# bellCPU.net
KiCad netlist of a schematic drawn in EAGLE
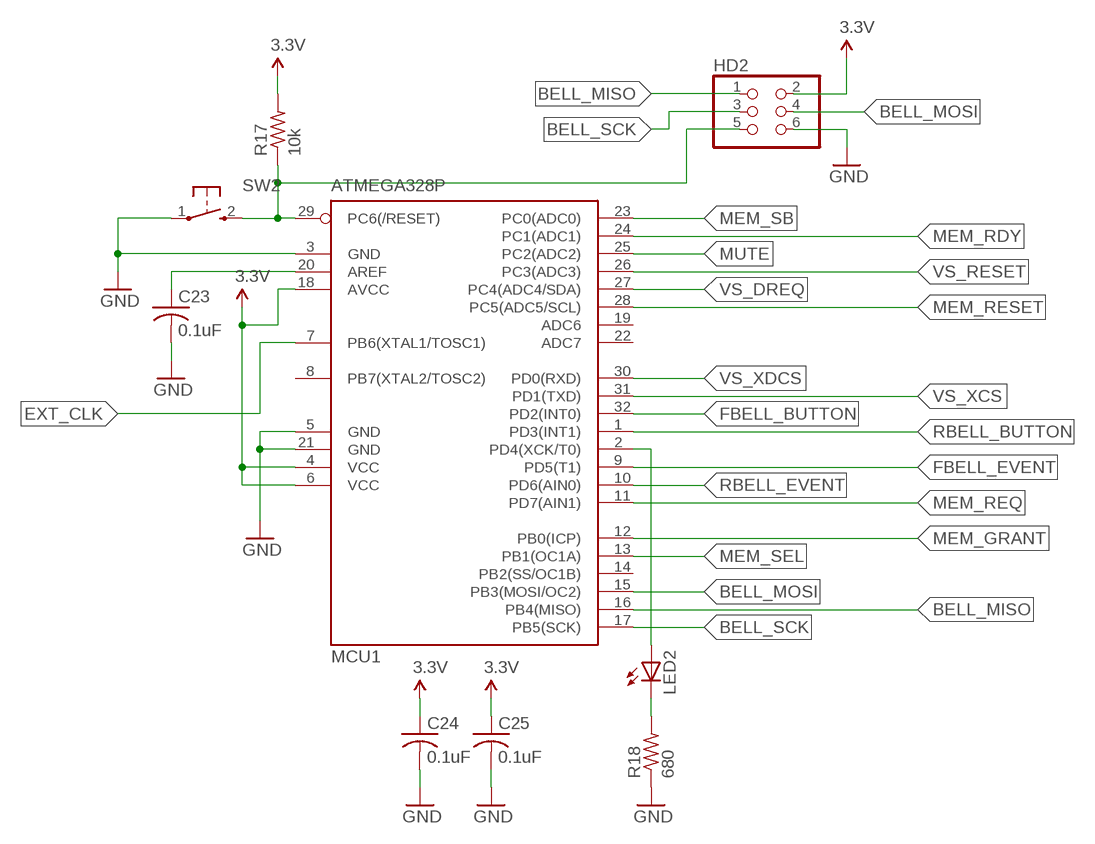
[diagram p0: schematic, sheet 1]

(export (version "E")
  (design (tool "Eeschema 10.0.6"))
  (components
    (comp (ref "C23")
      (value "0.1uF")
      (footprint "eagle-import:0603_CAP")
      (libsource (lib "eagle-import") (part "CAP0603"))
    )
    (comp (ref "C24")
      (value "0.1uF")
      (footprint "eagle-import:0603_CAP")
      (libsource (lib "eagle-import") (part "CAP0603"))
    )
    (comp (ref "C25")
      (value "0.1uF")
      (footprint "eagle-import:0603_CAP")
      (libsource (lib "eagle-import") (part "CAP0603"))
    )
    (comp (ref "HD2")
      (value "HEADER_2X3")
      (footprint "eagle-import:HEADER_2X3")
      (fields (field (name "MANF") "FCI"))
      (libsource (lib "eagle-import") (part "HEADER_2X3"))
    )
    (comp (ref "LED2")
      (value "LED0603")
      (footprint "eagle-import:0603_LED")
      (fields (field (name "MANF") "Avago Technologies"))
      (libsource (lib "eagle-import") (part "LED0603"))
    )
    (comp (ref "MCU1")
      (value "ATMEGA328P")
      (footprint "eagle-import:TQFP32-08")
      (fields (field (name "MANF") "Atmel"))
      (libsource (lib "eagle-import") (part "ATMEGA328P"))
    )
    (comp (ref "R17")
      (value "10k")
      (footprint "eagle-import:0603_RESISTOR")
      (libsource (lib "eagle-import") (part "RESISTOR0603"))
    )
    (comp (ref "R18")
      (value "680")
      (footprint "eagle-import:0603_RESISTOR")
      (libsource (lib "eagle-import") (part "RESISTOR0603"))
    )
    (comp (ref "SW2")
      (value "SWITCH")
      (footprint "eagle-import:SWITCH_TAC")
      (fields (field (name "MANF") "E-Switch"))
      (libsource (lib "eagle-import") (part "SWITCH"))
    )
  )
  (nets
    (net (code "1") (name "3.3V") (class "Default")
      (node (ref "C24") (pin "1") (pinfunction "1_1") (pintype "passive"))
      (node (ref "C25") (pin "1") (pinfunction "1_1") (pintype "passive"))
      (node (ref "HD2") (pin "2") (pinfunction "2_2") (pintype "passive"))
      (node (ref "MCU1") (pin "18") (pinfunction "AVCC_18") (pintype "power_in"))
      (node (ref "MCU1") (pin "4") (pinfunction "VCC_4") (pintype "power_in"))
      (node (ref "MCU1") (pin "6") (pinfunction "VCC_6") (pintype "power_in"))
      (node (ref "R17") (pin "2") (pinfunction "2_2") (pintype "passive"))
    )
    (net (code "2") (name "BELL_MISO") (class "Default")
      (node (ref "HD2") (pin "1") (pinfunction "1_1") (pintype "passive"))
      (node (ref "MCU1") (pin "16") (pinfunction "PB4(MISO)_16") (pintype "bidirectional"))
    )
    (net (code "3") (name "BELL_MOSI") (class "Default")
      (node (ref "HD2") (pin "4") (pinfunction "4_4") (pintype "passive"))
      (node (ref "MCU1") (pin "15") (pinfunction "PB3(MOSI/OC2)_15") (pintype "bidirectional"))
    )
    (net (code "4") (name "BELL_SCK") (class "Default")
      (node (ref "HD2") (pin "3") (pinfunction "3_3") (pintype "passive"))
      (node (ref "MCU1") (pin "17") (pinfunction "PB5(SCK)_17") (pintype "bidirectional"))
    )
    (net (code "5") (name "EXT_CLK") (class "Default")
      (node (ref "MCU1") (pin "7") (pinfunction "PB6(XTAL1/TOSC1)_7") (pintype "bidirectional"))
    )
    (net (code "6") (name "FBELL_BUTTON") (class "Default")
      (node (ref "MCU1") (pin "32") (pinfunction "PD2(INT0)_32") (pintype "bidirectional"))
    )
    (net (code "7") (name "FBELL_EVENT") (class "Default")
      (node (ref "MCU1") (pin "9") (pinfunction "PD5(T1)_9") (pintype "bidirectional"))
    )
    (net (code "8") (name "GND") (class "Default")
      (node (ref "C23") (pin "2") (pinfunction "2_2") (pintype "passive"))
      (node (ref "C24") (pin "2") (pinfunction "2_2") (pintype "passive"))
      (node (ref "C25") (pin "2") (pinfunction "2_2") (pintype "passive"))
      (node (ref "HD2") (pin "6") (pinfunction "6_6") (pintype "passive"))
      (node (ref "MCU1") (pin "21") (pinfunction "GND_21") (pintype "power_in"))
      (node (ref "MCU1") (pin "3") (pinfunction "GND_3") (pintype "power_in"))
      (node (ref "MCU1") (pin "5") (pinfunction "GND_5") (pintype "power_in"))
      (node (ref "R18") (pin "1") (pinfunction "1_1") (pintype "passive"))
      (node (ref "SW2") (pin "1") (pinfunction "1_1") (pintype "passive"))
    )
    (net (code "9") (name "MEM_GRANT") (class "Default")
      (node (ref "MCU1") (pin "12") (pinfunction "PB0(ICP)_12") (pintype "bidirectional"))
    )
    (net (code "10") (name "MEM_RDY") (class "Default")
      (node (ref "MCU1") (pin "24") (pinfunction "PC1(ADC1)_24") (pintype "bidirectional"))
    )
    (net (code "11") (name "MEM_REQ") (class "Default")
      (node (ref "MCU1") (pin "11") (pinfunction "PD7(AIN1)_11") (pintype "bidirectional"))
    )
    (net (code "12") (name "MEM_RESET") (class "Default")
      (node (ref "MCU1") (pin "28") (pinfunction "PC5(ADC5/SCL)_28") (pintype "bidirectional"))
    )
    (net (code "13") (name "MEM_SB") (class "Default")
      (node (ref "MCU1") (pin "23") (pinfunction "PC0(ADC0)_23") (pintype "bidirectional"))
    )
    (net (code "14") (name "MEM_SEL") (class "Default")
      (node (ref "MCU1") (pin "13") (pinfunction "PB1(OC1A)_13") (pintype "bidirectional"))
    )
    (net (code "15") (name "MUTE") (class "Default")
      (node (ref "MCU1") (pin "25") (pinfunction "PC2(ADC2)_25") (pintype "bidirectional"))
    )
    (net (code "16") (name "Net-(LED2-PadC)") (class "Default")
      (node (ref "LED2") (pin "C") (pinfunction "C_C") (pintype "passive"))
      (node (ref "R18") (pin "2") (pinfunction "2_2") (pintype "passive"))
    )
    (net (code "17") (name "Net-(MCU1-AREF)") (class "Default")
      (node (ref "C23") (pin "1") (pinfunction "1_1") (pintype "passive"))
      (node (ref "MCU1") (pin "20") (pinfunction "AREF_20") (pintype "passive"))
    )
    (net (code "18") (name "Net-(MCU1-PC6({slash}RESET))") (class "Default")
      (node (ref "HD2") (pin "5") (pinfunction "5_5") (pintype "passive"))
      (node (ref "MCU1") (pin "29") (pinfunction "PC6(/RESET)_29") (pintype "bidirectional"))
      (node (ref "R17") (pin "1") (pinfunction "1_1") (pintype "passive"))
      (node (ref "SW2") (pin "2") (pinfunction "2_2") (pintype "passive"))
    )
    (net (code "19") (name "Net-(MCU1-PD4(XCK{slash}T0))") (class "Default")
      (node (ref "LED2") (pin "A") (pinfunction "A_A") (pintype "passive"))
      (node (ref "MCU1") (pin "2") (pinfunction "PD4(XCK/T0)_2") (pintype "bidirectional"))
    )
    (net (code "20") (name "RBELL_BUTTON") (class "Default")
      (node (ref "MCU1") (pin "1") (pinfunction "PD3(INT1)_1") (pintype "bidirectional"))
    )
    (net (code "21") (name "RBELL_EVENT") (class "Default")
      (node (ref "MCU1") (pin "10") (pinfunction "PD6(AIN0)_10") (pintype "bidirectional"))
    )
    (net (code "22") (name "VS_DREQ") (class "Default")
      (node (ref "MCU1") (pin "27") (pinfunction "PC4(ADC4/SDA)_27") (pintype "bidirectional"))
    )
    (net (code "23") (name "VS_RESET") (class "Default")
      (node (ref "MCU1") (pin "26") (pinfunction "PC3(ADC3)_26") (pintype "bidirectional"))
    )
    (net (code "24") (name "VS_XCS") (class "Default")
      (node (ref "MCU1") (pin "31") (pinfunction "PD1(TXD)_31") (pintype "bidirectional"))
    )
    (net (code "25") (name "VS_XDCS") (class "Default")
      (node (ref "MCU1") (pin "30") (pinfunction "PD0(RXD)_30") (pintype "bidirectional"))
    )
    (net (code "26") (name "unconnected-(MCU1-ADC6-Pad19)") (class "Default")
      (node (ref "MCU1") (pin "19") (pinfunction "ADC6_19") (pintype "bidirectional"))
    )
    (net (code "27") (name "unconnected-(MCU1-ADC7-Pad22)") (class "Default")
      (node (ref "MCU1") (pin "22") (pinfunction "ADC7_22") (pintype "bidirectional"))
    )
    (net (code "28") (name "unconnected-(MCU1-PB2(SS{slash}OC1B)-Pad14)") (class "Default")
      (node (ref "MCU1") (pin "14") (pinfunction "PB2(SS/OC1B)_14") (pintype "bidirectional"))
    )
    (net (code "29") (name "unconnected-(MCU1-PB7(XTAL2{slash}TOSC2)-Pad8)") (class "Default")
      (node (ref "MCU1") (pin "8") (pinfunction "PB7(XTAL2/TOSC2)_8") (pintype "bidirectional"))
    )
  )
)
